# Power.net
KiCad netlist of a schematic drawn in Altium Designer
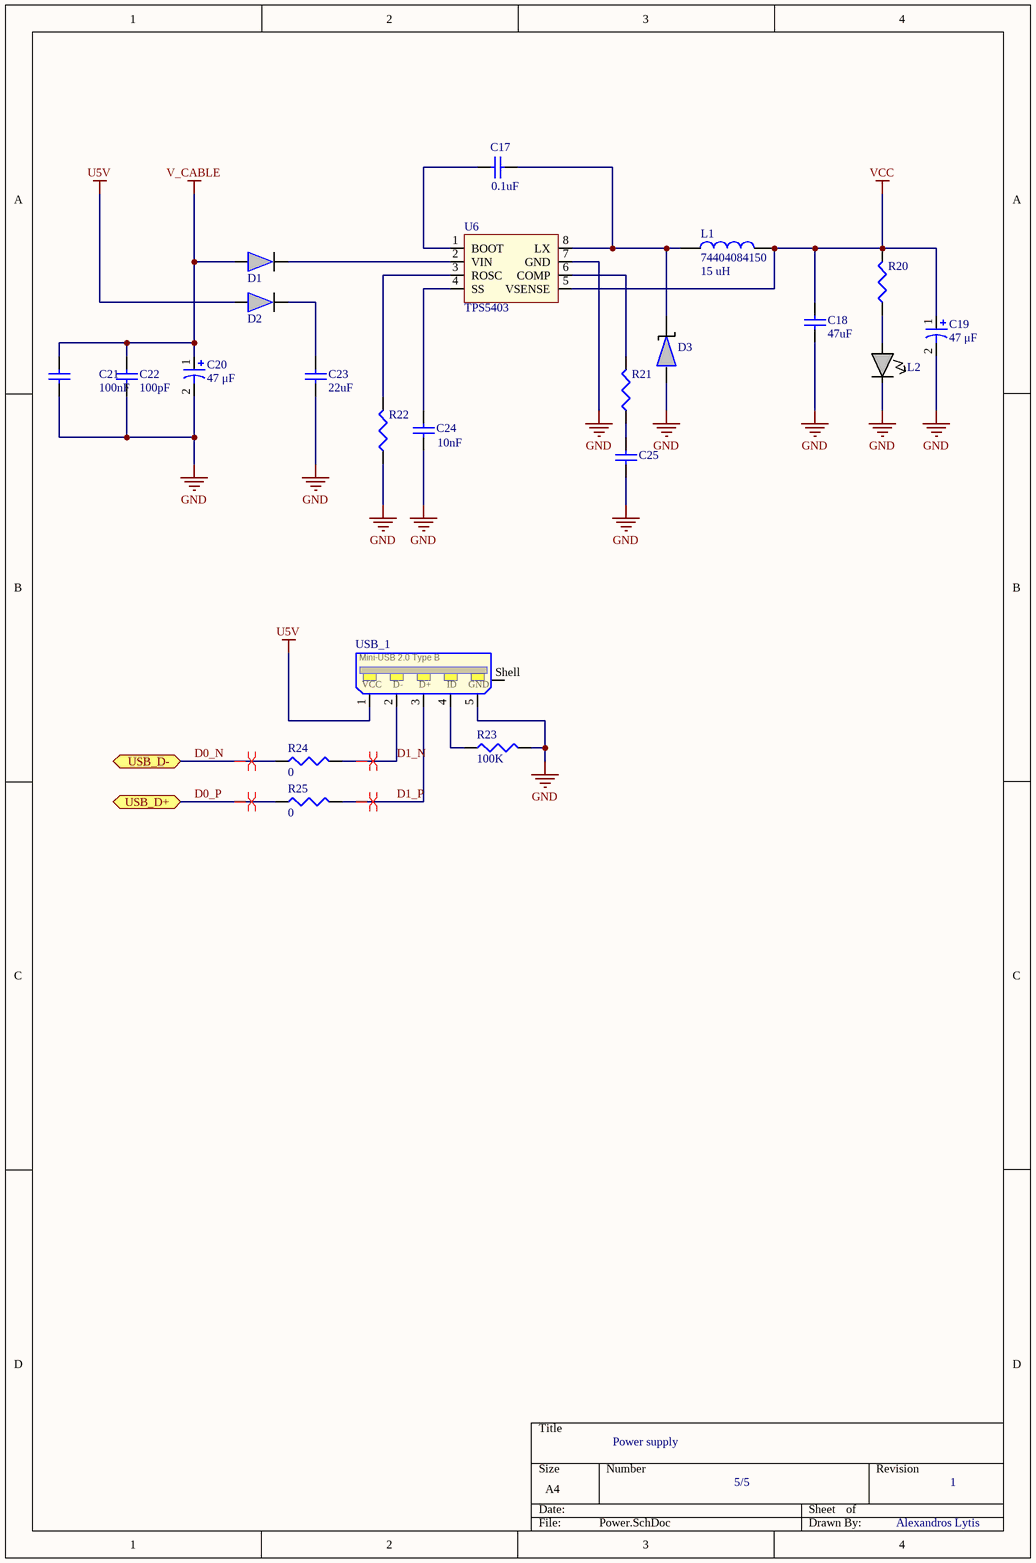
[diagram p0: Power.SchDoc]

(export (version "E")
  (design (tool "Eeschema 10.0.6"))
  (components
    (comp (ref "C17")
      (value "0.1uF")
      (footprint "CAP0603")
      (description "Capacitor (Semiconductor SIM Model)")
      (fields (field (name "Comment") "Cap Semi") (field (name "PUBLISHER") "Altium Limited"))
      (libsource (lib "Miscellaneous Devices") (part "Cap Semi"))
    )
    (comp (ref "C18")
      (value "47uF")
      (footprint "CAP0603")
      (description "Capacitor (Semiconductor SIM Model)")
      (fields (field (name "Comment") "Cap Semi") (field (name "PUBLISHER") "Altium Limited"))
      (libsource (lib "Miscellaneous Devices") (part "Cap Semi"))
    )
    (comp (ref "C19")
      (value "47 μF")
      (footprint "WCAP-PSLP 6.3x5.8x2.2")
      (description "WCAP-PSLP Aluminum Polymer Capacitors , 47 μF; + / - 20%; 16 V , 6,3 x 5,8")
      (fields
        (field (name "MANUFACTURER") "Wurth Elektronik")
        (field (name "PARTNO") "875105344006")
        (field (name "E-MAIL") "libraries@we-online.com")
        (field (name "CREATED BY") "Karrer Zheng")
      )
      (libsource (lib "WCAP-PSLP_rev15a") (part "WCAP-PSLP 6.3x5.8x2.2 875105344006"))
    )
    (comp (ref "C20")
      (value "47 μF")
      (footprint "WCAP-PSLP 6.3x5.8x2.2")
      (description "WCAP-PSLP Aluminum Polymer Capacitors , 47 μF; + / - 20%; 16 V , 6,3 x 5,8")
      (fields
        (field (name "MANUFACTURER") "Wurth Elektronik")
        (field (name "PARTNO") "875105344006")
        (field (name "E-MAIL") "libraries@we-online.com")
        (field (name "CREATED BY") "Karrer Zheng")
      )
      (libsource (lib "WCAP-PSLP_rev15a") (part "WCAP-PSLP 6.3x5.8x2.2 875105344006"))
    )
    (comp (ref "C21")
      (value "100nF")
      (footprint "CAP0603")
      (description "Capacitor (Semiconductor SIM Model)")
      (fields (field (name "Comment") "Cap Semi") (field (name "PUBLISHER") "Altium Limited"))
      (libsource (lib "Miscellaneous Devices") (part "Cap Semi"))
    )
    (comp (ref "C22")
      (value "100pF")
      (footprint "CAP0603")
      (description "Capacitor (Semiconductor SIM Model)")
      (fields (field (name "Comment") "Cap Semi") (field (name "PUBLISHER") "Altium Limited"))
      (libsource (lib "Miscellaneous Devices") (part "Cap Semi"))
    )
    (comp (ref "C23")
      (value "22uF")
      (footprint "CAP0603")
      (description "Capacitor (Semiconductor SIM Model)")
      (fields (field (name "Comment") "Cap Semi") (field (name "PUBLISHER") "Altium Limited"))
      (libsource (lib "Miscellaneous Devices") (part "Cap Semi"))
    )
    (comp (ref "C24")
      (value "10nF")
      (footprint "CAP0603")
      (description "Capacitor (Semiconductor SIM Model)")
      (fields (field (name "Comment") "Cap Semi") (field (name "PUBLISHER") "Altium Limited"))
      (libsource (lib "Miscellaneous Devices") (part "Cap Semi"))
    )
    (comp (ref "C25")
      (value "Cap Semi")
      (footprint "CAP0603")
      (description "Capacitor (Semiconductor SIM Model)")
      (fields (field (name "PUBLISHER") "Altium Limited"))
      (libsource (lib "Miscellaneous Devices") (part "Cap Semi"))
    )
    (comp (ref "D1")
      (value "MBR180S1 schottky")
      (footprint "MBR180S1")
      (libsource (lib "Custom_Libraries") (part "MRB180S1 schottky"))
    )
    (comp (ref "D2")
      (value "MBR180S1 schottky")
      (footprint "MBR180S1")
      (libsource (lib "Custom_Libraries") (part "MRB180S1 schottky"))
    )
    (comp (ref "D3")
      (value "schottky Diode")
      (footprint "DIOM1709X08N")
      (libsource (lib "Custom_Libraries") (part "SMD_schottky_CDBU0130L"))
    )
    (comp (ref "L1")
      (value "74404084150")
      (footprint "WE-LQS_8040")
      (description "WE-LQS SMD Power Inductor, size 8040, 15 uH")
      (fields (field (name "ALTIUM_VALUE") "15 uH") (field (name "PUBLISHER") "Wurth Elektronik"))
      (libsource (lib "ALTIUM-WE-LQS-rev16b") (part "74404084150"))
    )
    (comp (ref "L2")
      (value "LED_1.6x0.8mm")
      (footprint "J1-0603")
      (libsource (lib "Custom_Libraries") (part "LED_1.6x0.8mm"))
    )
    (comp (ref "R20")
      (value "Res3")
      (footprint "RES0603")
      (description "Resistor")
      (fields (field (name "PUBLISHER") "Altium Limited"))
      (libsource (lib "Miscellaneous Devices") (part "Res3"))
    )
    (comp (ref "R21")
      (value "Res3")
      (footprint "RES0603")
      (description "Resistor")
      (fields (field (name "PUBLISHER") "Altium Limited"))
      (libsource (lib "Miscellaneous Devices") (part "Res3"))
    )
    (comp (ref "R22")
      (value "Res3")
      (footprint "RES0603")
      (description "Resistor")
      (fields (field (name "PUBLISHER") "Altium Limited"))
      (libsource (lib "Miscellaneous Devices") (part "Res3"))
    )
    (comp (ref "R23")
      (value "100K")
      (footprint "RES0603")
      (description "Resistor")
      (fields (field (name "Comment") "Res3") (field (name "PUBLISHER") "Altium Limited"))
      (libsource (lib "Miscellaneous Devices") (part "Res3"))
    )
    (comp (ref "R24")
      (value "0")
      (footprint "RES0603")
      (description "Resistor")
      (fields (field (name "Comment") "Res3") (field (name "PUBLISHER") "Altium Limited"))
      (libsource (lib "Miscellaneous Devices") (part "Res3"))
    )
    (comp (ref "R25")
      (value "0")
      (footprint "RES0603")
      (description "Resistor")
      (fields (field (name "Comment") "Res3") (field (name "PUBLISHER") "Altium Limited"))
      (libsource (lib "Miscellaneous Devices") (part "Res3"))
    )
    (comp (ref "U6")
      (value "TPS5403")
      (footprint "SOIC127P600X175-8M")
      (description "switching power-3.3V")
      (libsource (lib "Custom_Libraries") (part "TPS5403"))
    )
    (comp (ref "USB_1")
      (value "65100516121")
      (footprint "65100516121")
      (description "WR-COM Mini USB 2.0 Type B SMT Horizontal 5 Contacts")
      (fields (field (name "PUBLISHER") "Wurth Elektronik"))
      (libsource (lib "ALTIUM-WR-COM-rev16d") (part "65100516121"))
    )
  )
  (nets
    (net (code "1") (name "/D0_N") (class "Default")
      (node (ref "R24") (pin "1") (pinfunction "1_1") (pintype "passive"))
    )
    (net (code "2") (name "/D0_P") (class "Default")
      (node (ref "R25") (pin "1") (pinfunction "1_1") (pintype "passive"))
    )
    (net (code "3") (name "/D1_N") (class "Default")
      (node (ref "R24") (pin "2") (pinfunction "2_2") (pintype "passive"))
      (node (ref "USB_1") (pin "2") (pinfunction "D-_2") (pintype "passive"))
    )
    (net (code "4") (name "/D1_P") (class "Default")
      (node (ref "R25") (pin "2") (pinfunction "2_2") (pintype "passive"))
      (node (ref "USB_1") (pin "3") (pinfunction "D+_3") (pintype "passive"))
    )
    (net (code "5") (name "GND") (class "Default")
      (node (ref "C18") (pin "1") (pinfunction "1_1") (pintype "passive"))
      (node (ref "C19") (pin "2") (pinfunction "2_2") (pintype "passive"))
      (node (ref "C20") (pin "2") (pinfunction "2_2") (pintype "passive"))
      (node (ref "C21") (pin "1") (pinfunction "1_1") (pintype "passive"))
      (node (ref "C22") (pin "1") (pinfunction "1_1") (pintype "passive"))
      (node (ref "C23") (pin "1") (pinfunction "1_1") (pintype "passive"))
      (node (ref "C24") (pin "1") (pinfunction "1_1") (pintype "passive"))
      (node (ref "C25") (pin "1") (pinfunction "1_1") (pintype "passive"))
      (node (ref "D3") (pin "2") (pinfunction "anode_2") (pintype "passive"))
      (node (ref "L2") (pin "2") (pintype "passive"))
      (node (ref "R22") (pin "1") (pinfunction "1_1") (pintype "passive"))
      (node (ref "R23") (pin "2") (pinfunction "2_2") (pintype "passive"))
      (node (ref "U6") (pin "7") (pinfunction "GND_7") (pintype "passive"))
      (node (ref "USB_1") (pin "5") (pinfunction "GND_5") (pintype "passive"))
    )
    (net (code "6") (name "Net-(C25-Pad2)") (class "Default")
      (node (ref "C25") (pin "2") (pinfunction "2_2") (pintype "passive"))
      (node (ref "R21") (pin "1") (pinfunction "1_1") (pintype "passive"))
    )
    (net (code "7") (name "Net-(D1-Cathode)") (class "Default")
      (node (ref "D1") (pin "1") (pinfunction "Cathode_1") (pintype "passive"))
      (node (ref "U6") (pin "2") (pinfunction "VIN_2") (pintype "passive"))
    )
    (net (code "8") (name "Net-(D2-Cathode)") (class "Default")
      (node (ref "C23") (pin "2") (pinfunction "2_2") (pintype "passive"))
      (node (ref "D2") (pin "1") (pinfunction "Cathode_1") (pintype "passive"))
    )
    (net (code "9") (name "Net-(D3-Cathode)") (class "Default")
      (node (ref "C17") (pin "1") (pinfunction "1_1") (pintype "passive"))
      (node (ref "D3") (pin "1") (pinfunction "Cathode_1") (pintype "passive"))
      (node (ref "L1") (pin "1") (pinfunction "1_1") (pintype "passive"))
      (node (ref "U6") (pin "8") (pinfunction "LX_8") (pintype "passive"))
    )
    (net (code "10") (name "Net-(L2-Pad1)") (class "Default")
      (node (ref "L2") (pin "1") (pintype "passive"))
      (node (ref "R20") (pin "1") (pinfunction "1_1") (pintype "passive"))
    )
    (net (code "11") (name "Net-(U6-BOOT)") (class "Default")
      (node (ref "C17") (pin "2") (pinfunction "2_2") (pintype "passive"))
      (node (ref "U6") (pin "1") (pinfunction "BOOT_1") (pintype "passive"))
    )
    (net (code "12") (name "Net-(U6-COMP)") (class "Default")
      (node (ref "R21") (pin "2") (pinfunction "2_2") (pintype "passive"))
      (node (ref "U6") (pin "6") (pinfunction "COMP_6") (pintype "passive"))
    )
    (net (code "13") (name "Net-(U6-ROSC)") (class "Default")
      (node (ref "R22") (pin "2") (pinfunction "2_2") (pintype "passive"))
      (node (ref "U6") (pin "3") (pinfunction "ROSC_3") (pintype "passive"))
    )
    (net (code "14") (name "Net-(U6-SS)") (class "Default")
      (node (ref "C24") (pin "2") (pinfunction "2_2") (pintype "passive"))
      (node (ref "U6") (pin "4") (pinfunction "SS_4") (pintype "passive"))
    )
    (net (code "15") (name "Net-(USB_1-ID)") (class "Default")
      (node (ref "R23") (pin "1") (pinfunction "1_1") (pintype "passive"))
      (node (ref "USB_1") (pin "4") (pinfunction "ID_4") (pintype "passive"))
    )
    (net (code "16") (name "U5V") (class "Default")
      (node (ref "D2") (pin "2") (pinfunction "Anode_2") (pintype "passive"))
      (node (ref "USB_1") (pin "1") (pinfunction "VCC_1") (pintype "passive"))
    )
    (net (code "17") (name "VCC") (class "Default")
      (node (ref "C18") (pin "2") (pinfunction "2_2") (pintype "passive"))
      (node (ref "C19") (pin "1") (pinfunction "1_1") (pintype "passive"))
      (node (ref "L1") (pin "2") (pinfunction "2_2") (pintype "passive"))
      (node (ref "R20") (pin "2") (pinfunction "2_2") (pintype "passive"))
      (node (ref "U6") (pin "5") (pinfunction "VSENSE_5") (pintype "passive"))
    )
    (net (code "18") (name "V_CABLE") (class "Default")
      (node (ref "C20") (pin "1") (pinfunction "1_1") (pintype "passive"))
      (node (ref "C21") (pin "2") (pinfunction "2_2") (pintype "passive"))
      (node (ref "C22") (pin "2") (pinfunction "2_2") (pintype "passive"))
      (node (ref "D1") (pin "2") (pinfunction "Anode_2") (pintype "passive"))
    )
    (net (code "19") (name "unconnected-(USB_1-PadShell)") (class "Default")
      (node (ref "USB_1") (pin "Shell") (pinfunction "Shell_Shell") (pintype "passive"))
    )
  )
)
